# Register_Connector.net
KiCad netlist of a schematic drawn in Altium Designer
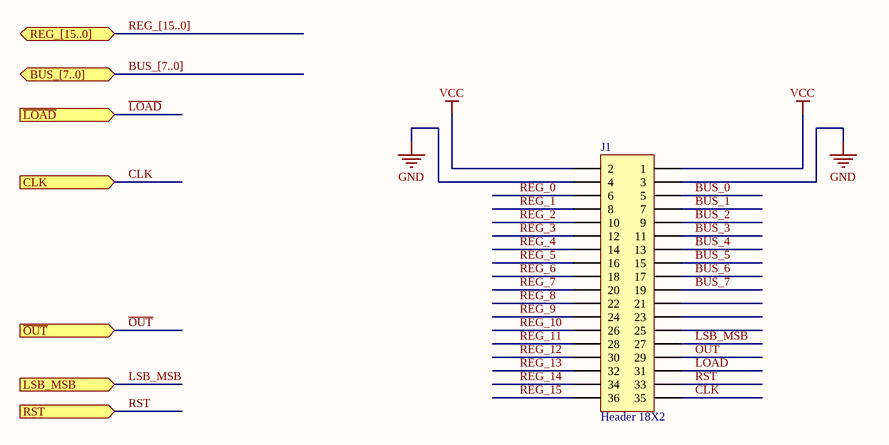
[diagram p0: Register Connector.SchDoc]

(export (version "E")
  (design (tool "Eeschema 10.0.6"))
  (components
    (comp (ref "J1")
      (value "Header 18X2")
      (footprint "HDR2X18")
      (description "Header, 18-Pin, Dual row")
      (fields (field (name "PUBLISHER") "Altium Limited"))
      (libsource (lib "Miscellaneous Connectors") (part "Header 18X2"))
    )
  )
  (nets
    (net (code "1") (name "/BUS_0") (class "Default")
      (node (ref "J1") (pin "5") (pinfunction "5_5") (pintype "passive"))
    )
    (net (code "2") (name "/BUS_1") (class "Default")
      (node (ref "J1") (pin "7") (pinfunction "7_7") (pintype "passive"))
    )
    (net (code "3") (name "/BUS_2") (class "Default")
      (node (ref "J1") (pin "9") (pinfunction "9_9") (pintype "passive"))
    )
    (net (code "4") (name "/BUS_3") (class "Default")
      (node (ref "J1") (pin "11") (pinfunction "11_11") (pintype "passive"))
    )
    (net (code "5") (name "/BUS_4") (class "Default")
      (node (ref "J1") (pin "13") (pinfunction "13_13") (pintype "passive"))
    )
    (net (code "6") (name "/BUS_5") (class "Default")
      (node (ref "J1") (pin "15") (pinfunction "15_15") (pintype "passive"))
    )
    (net (code "7") (name "/BUS_6") (class "Default")
      (node (ref "J1") (pin "17") (pinfunction "17_17") (pintype "passive"))
    )
    (net (code "8") (name "/BUS_7") (class "Default")
      (node (ref "J1") (pin "19") (pinfunction "19_19") (pintype "passive"))
    )
    (net (code "10") (name "/CLK") (class "Default")
      (node (ref "J1") (pin "35") (pinfunction "35_35") (pintype "passive"))
    )
    (net (code "11") (name "/LSB_MSB") (class "Default")
      (node (ref "J1") (pin "27") (pinfunction "27_27") (pintype "passive"))
    )
    (net (code "12") (name "/REG_0") (class "Default")
      (node (ref "J1") (pin "6") (pinfunction "6_6") (pintype "passive"))
    )
    (net (code "13") (name "/REG_1") (class "Default")
      (node (ref "J1") (pin "8") (pinfunction "8_8") (pintype "passive"))
    )
    (net (code "14") (name "/REG_2") (class "Default")
      (node (ref "J1") (pin "10") (pinfunction "10_10") (pintype "passive"))
    )
    (net (code "15") (name "/REG_3") (class "Default")
      (node (ref "J1") (pin "12") (pinfunction "12_12") (pintype "passive"))
    )
    (net (code "16") (name "/REG_4") (class "Default")
      (node (ref "J1") (pin "14") (pinfunction "14_14") (pintype "passive"))
    )
    (net (code "17") (name "/REG_5") (class "Default")
      (node (ref "J1") (pin "16") (pinfunction "16_16") (pintype "passive"))
    )
    (net (code "18") (name "/REG_6") (class "Default")
      (node (ref "J1") (pin "18") (pinfunction "18_18") (pintype "passive"))
    )
    (net (code "19") (name "/REG_7") (class "Default")
      (node (ref "J1") (pin "20") (pinfunction "20_20") (pintype "passive"))
    )
    (net (code "20") (name "/REG_8") (class "Default")
      (node (ref "J1") (pin "22") (pinfunction "22_22") (pintype "passive"))
    )
    (net (code "21") (name "/REG_9") (class "Default")
      (node (ref "J1") (pin "24") (pinfunction "24_24") (pintype "passive"))
    )
    (net (code "22") (name "/REG_10") (class "Default")
      (node (ref "J1") (pin "26") (pinfunction "26_26") (pintype "passive"))
    )
    (net (code "23") (name "/REG_11") (class "Default")
      (node (ref "J1") (pin "28") (pinfunction "28_28") (pintype "passive"))
    )
    (net (code "24") (name "/REG_12") (class "Default")
      (node (ref "J1") (pin "30") (pinfunction "30_30") (pintype "passive"))
    )
    (net (code "25") (name "/REG_13") (class "Default")
      (node (ref "J1") (pin "32") (pinfunction "32_32") (pintype "passive"))
    )
    (net (code "26") (name "/REG_14") (class "Default")
      (node (ref "J1") (pin "34") (pinfunction "34_34") (pintype "passive"))
    )
    (net (code "27") (name "/REG_15") (class "Default")
      (node (ref "J1") (pin "36") (pinfunction "36_36") (pintype "passive"))
    )
    (net (code "29") (name "/RST") (class "Default")
      (node (ref "J1") (pin "33") (pinfunction "33_33") (pintype "passive"))
    )
    (net (code "30") (name "/~{LOAD}") (class "Default")
      (node (ref "J1") (pin "31") (pinfunction "31_31") (pintype "passive"))
    )
    (net (code "31") (name "/~{OUT}") (class "Default")
      (node (ref "J1") (pin "29") (pinfunction "29_29") (pintype "passive"))
    )
    (net (code "32") (name "GND") (class "Default")
      (node (ref "J1") (pin "3") (pinfunction "3_3") (pintype "passive"))
      (node (ref "J1") (pin "4") (pinfunction "4_4") (pintype "passive"))
    )
    (net (code "33") (name "VCC") (class "Default")
      (node (ref "J1") (pin "1") (pinfunction "1_1") (pintype "passive"))
      (node (ref "J1") (pin "2") (pinfunction "2_2") (pintype "passive"))
    )
    (net (code "34") (name "unconnected-(J1-Pad21)") (class "Default")
      (node (ref "J1") (pin "21") (pinfunction "21_21") (pintype "passive"))
    )
    (net (code "35") (name "unconnected-(J1-Pad23)") (class "Default")
      (node (ref "J1") (pin "23") (pinfunction "23_23") (pintype "passive"))
    )
    (net (code "36") (name "unconnected-(J1-Pad25)") (class "Default")
      (node (ref "J1") (pin "25") (pinfunction "25_25") (pintype "passive"))
    )
  )
)
